# Directional_Coupler.net
KiCad netlist of a schematic drawn in Altium Designer
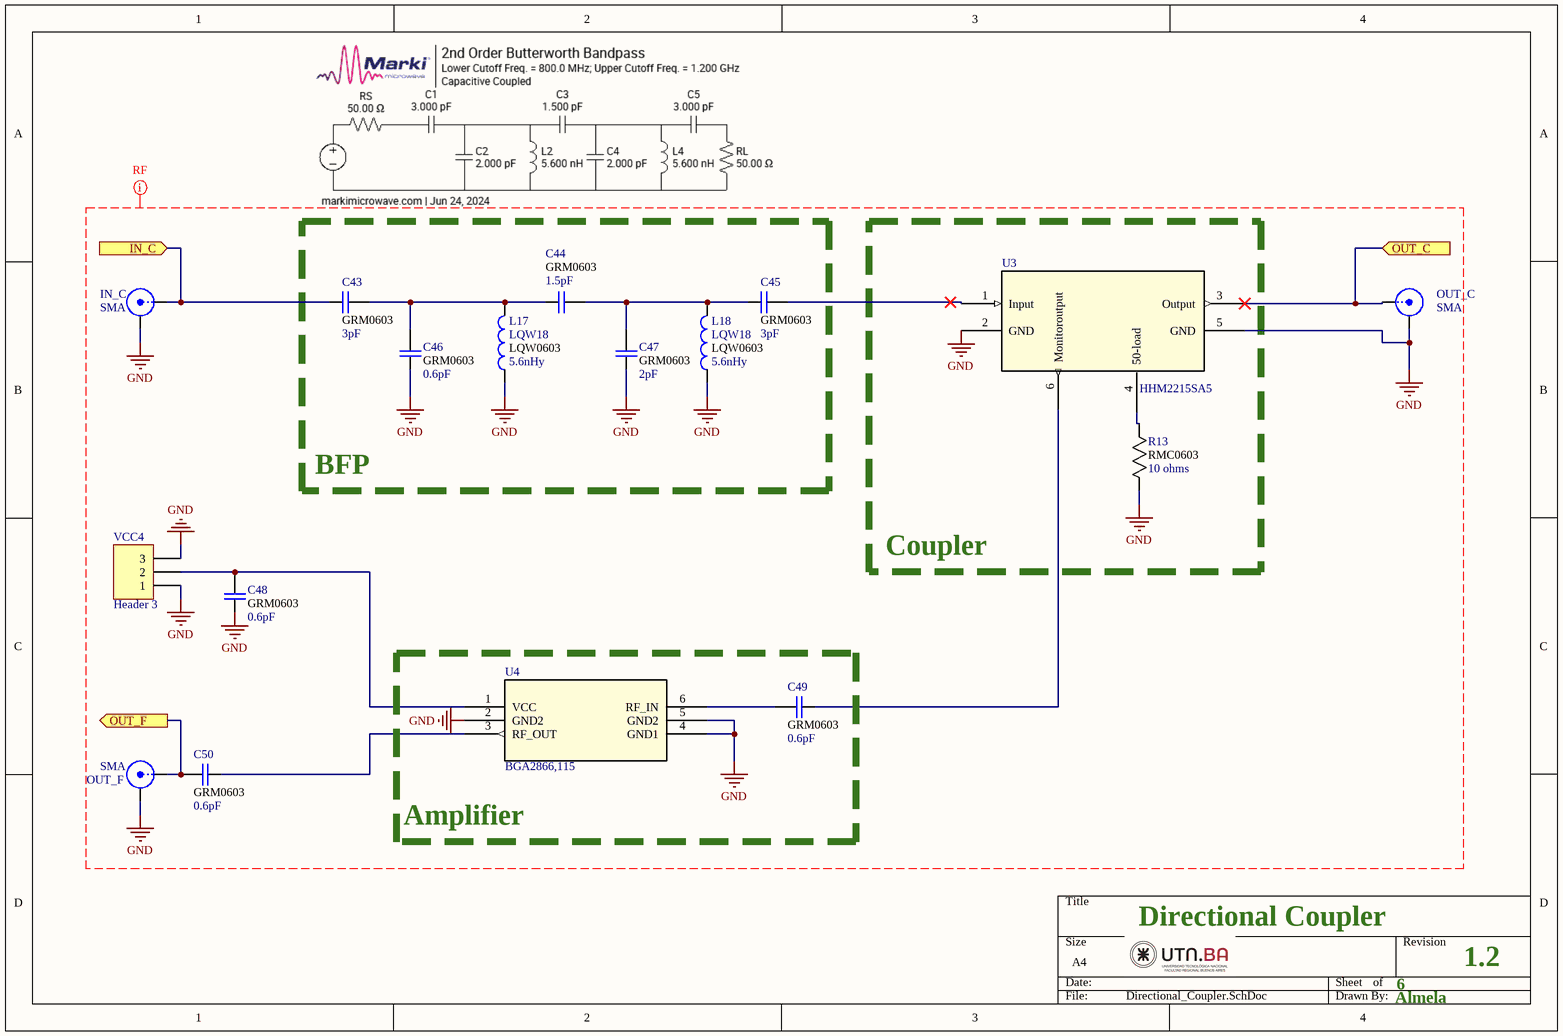
[diagram p0: Directional_Coupler.SchDoc]

(export (version "E")
  (design (tool "Eeschema 10.0.6"))
  (components
    (comp (ref "C43")
      (value "3pF")
      (footprint "GRM0603")
      (description "Capacitor GRM18 0603")
      (fields (field (name "Comment") "Cap 0603") (field (name "PUBLISHER") "Altium Limited"))
      (libsource (lib "Radar_RF_EAIII") (part "Cap"))
    )
    (comp (ref "C44")
      (value "1.5pF")
      (footprint "GRM0603")
      (description "Capacitor GRM18 0603")
      (fields (field (name "Comment") "Cap 0603") (field (name "PUBLISHER") "Altium Limited"))
      (libsource (lib "Radar_RF_EAIII") (part "Cap"))
    )
    (comp (ref "C45")
      (value "3pF")
      (footprint "GRM0603")
      (description "Capacitor GRM18 0603")
      (fields (field (name "Comment") "Cap 0603") (field (name "PUBLISHER") "Altium Limited"))
      (libsource (lib "Radar_RF_EAIII") (part "Cap"))
    )
    (comp (ref "C46")
      (value "0.6pF")
      (footprint "GRM0603")
      (description "Capacitor GRM18 0603")
      (fields (field (name "Comment") "Cap 0603") (field (name "PUBLISHER") "Altium Limited"))
      (libsource (lib "Radar_RF_EAIII") (part "Cap"))
    )
    (comp (ref "C47")
      (value "2pF")
      (footprint "GRM0603")
      (description "Capacitor GRM18 0603")
      (fields (field (name "Comment") "Cap 0603") (field (name "PUBLISHER") "Altium Limited"))
      (libsource (lib "Radar_RF_EAIII") (part "Cap"))
    )
    (comp (ref "C48")
      (value "0.6pF")
      (footprint "GRM0603")
      (description "Capacitor GRM18 0603")
      (fields (field (name "Comment") "Cap 0603") (field (name "PUBLISHER") "Altium Limited"))
      (libsource (lib "Radar_RF_EAIII") (part "Cap"))
    )
    (comp (ref "C49")
      (value "0.6pF")
      (footprint "GRM0603")
      (description "Capacitor GRM18 0603")
      (fields (field (name "Comment") "Cap 0603") (field (name "PUBLISHER") "Altium Limited"))
      (libsource (lib "Radar_RF_EAIII") (part "Cap"))
    )
    (comp (ref "C50")
      (value "0.6pF")
      (footprint "GRM0603")
      (description "Capacitor GRM18 0603")
      (fields (field (name "Comment") "Cap 0603") (field (name "PUBLISHER") "Altium Limited"))
      (libsource (lib "Radar_RF_EAIII") (part "Cap"))
    )
    (comp (ref "IN_C")
      (value "SMA")
      (footprint "SMA-142-0701-851")
      (description "SMA Straight Connector")
      (fields (field (name "PUBLISHER") "Altium Limited"))
      (libsource (lib "Radar_RF_EAIII") (part "SMA"))
    )
    (comp (ref "L17")
      (value "LQW18")
      (footprint "INDC1608X100N")
      (description "Ind RF Chip Wirewound 18nH 5% 100MHz 40Q-Factor 550mA 0603 Paper T/R")
      (fields
        (field (name "MP") "LQW18AN18NJ00D")
        (field (name "PARAMETER 1") "LQW0603")
        (field (name "ALTIUM_VALUE") "5.6nHy")
      )
      (libsource (lib "Radar_RF_EAIII") (part "LQW18"))
    )
    (comp (ref "L18")
      (value "LQW18")
      (footprint "INDC1608X100N")
      (description "Ind RF Chip Wirewound 18nH 5% 100MHz 40Q-Factor 550mA 0603 Paper T/R")
      (fields
        (field (name "MP") "LQW18AN18NJ00D")
        (field (name "PARAMETER 1") "LQW0603")
        (field (name "ALTIUM_VALUE") "5.6nHy")
      )
      (libsource (lib "Radar_RF_EAIII") (part "LQW18"))
    )
    (comp (ref "OUT_C")
      (value "SMA")
      (footprint "SMA-142-0701-851")
      (description "SMA Straight Connector")
      (fields (field (name "PUBLISHER") "Altium Limited"))
      (libsource (lib "Radar_RF_EAIII") (part "SMA"))
    )
    (comp (ref "OUT_F")
      (value "SMA")
      (footprint "SMA-142-0701-851")
      (description "SMB Straight Connector")
      (fields (field (name "PUBLISHER") "Altium Limited"))
      (libsource (lib "PCB_Project") (part "SMB"))
    )
    (comp (ref "R13")
      (value "10 ohms")
      (footprint "RMC0603")
      (description "Resistor RMC0603")
      (fields (field (name "Comment") "Resistor"))
      (libsource (lib "Radar_RF_EAIII") (part "Resistor"))
    )
    (comp (ref "U3")
      (value "HHM2215SA5")
      (footprint "HHM-6_1P6X0P8")
      (description "No Description Available")
      (libsource (lib "Radar_RF_EAIII") (part "HHM2215SA5"))
    )
    (comp (ref "U4")
      (value "BGA2866,115")
      (footprint "SOT363_NXP")
      (description "No Description Available")
      (libsource (lib "Radar_RF_EAIII") (part "BGA2866,115"))
    )
    (comp (ref "VCC4")
      (value "Header 3")
      (footprint "HDR1X3")
      (description "Header, 3-Pin")
      (fields (field (name "PUBLISHER") "Altium Limited"))
      (libsource (lib "Miscellaneous Connectors") (part "Header 3"))
    )
  )
  (nets
    (net (code "1") (name "/IN_C") (class "Default")
      (node (ref "C43") (pin "1") (pinfunction "1_1") (pintype "passive"))
      (node (ref "IN_C") (pin "1") (pinfunction "X_1") (pintype "passive"))
    )
    (net (code "2") (name "/OUT_C") (class "Default")
      (node (ref "OUT_C") (pin "1") (pinfunction "X_1") (pintype "passive"))
      (node (ref "U3") (pin "3") (pinfunction "Output_3") (pintype "output"))
    )
    (net (code "3") (name "/OUT_F") (class "Default")
      (node (ref "C50") (pin "2") (pinfunction "2_2") (pintype "passive"))
      (node (ref "OUT_F") (pin "1") (pinfunction "X_1") (pintype "passive"))
    )
    (net (code "4") (name "GND") (class "Default")
      (node (ref "C46") (pin "1") (pinfunction "1_1") (pintype "passive"))
      (node (ref "C47") (pin "1") (pinfunction "1_1") (pintype "passive"))
      (node (ref "C48") (pin "1") (pinfunction "1_1") (pintype "passive"))
      (node (ref "IN_C") (pin "2") (pinfunction "Y_2") (pintype "passive"))
      (node (ref "L17") (pin "1") (pinfunction "1_1") (pintype "passive"))
      (node (ref "L18") (pin "1") (pinfunction "1_1") (pintype "passive"))
      (node (ref "OUT_C") (pin "2") (pinfunction "Y_2") (pintype "passive"))
      (node (ref "OUT_F") (pin "2") (pinfunction "Y_2") (pintype "passive"))
      (node (ref "R13") (pin "1") (pinfunction "1_1") (pintype "passive"))
      (node (ref "U3") (pin "2") (pinfunction "GND_2") (pintype "power_in"))
      (node (ref "U3") (pin "5") (pinfunction "GND_5") (pintype "power_in"))
      (node (ref "U4") (pin "2") (pinfunction "GND2_2") (pintype "power_in"))
      (node (ref "U4") (pin "4") (pinfunction "GND1_4") (pintype "power_in"))
      (node (ref "U4") (pin "5") (pinfunction "GND2_5") (pintype "power_in"))
      (node (ref "VCC4") (pin "1") (pinfunction "1_1") (pintype "passive"))
      (node (ref "VCC4") (pin "3") (pinfunction "3_3") (pintype "passive"))
    )
    (net (code "5") (name "Net-(C43-Pad2)") (class "Default")
      (node (ref "C43") (pin "2") (pinfunction "2_2") (pintype "passive"))
      (node (ref "C44") (pin "1") (pinfunction "1_1") (pintype "passive"))
      (node (ref "C46") (pin "2") (pinfunction "2_2") (pintype "passive"))
      (node (ref "L17") (pin "2") (pinfunction "2_2") (pintype "passive"))
    )
    (net (code "6") (name "Net-(C44-Pad2)") (class "Default")
      (node (ref "C44") (pin "2") (pinfunction "2_2") (pintype "passive"))
      (node (ref "C45") (pin "1") (pinfunction "1_1") (pintype "passive"))
      (node (ref "C47") (pin "2") (pinfunction "2_2") (pintype "passive"))
      (node (ref "L18") (pin "2") (pinfunction "2_2") (pintype "passive"))
    )
    (net (code "7") (name "Net-(U3-50-load)") (class "Default")
      (node (ref "R13") (pin "2") (pinfunction "2_2") (pintype "passive"))
      (node (ref "U3") (pin "4") (pinfunction "50-load_4") (pintype "passive"))
    )
    (net (code "8") (name "Net-(U3-Input)") (class "Default")
      (node (ref "C45") (pin "2") (pinfunction "2_2") (pintype "passive"))
      (node (ref "U3") (pin "1") (pinfunction "Input_1") (pintype "input"))
    )
    (net (code "9") (name "Net-(U3-Monitoroutput)") (class "Default")
      (node (ref "C49") (pin "1") (pinfunction "1_1") (pintype "passive"))
      (node (ref "U3") (pin "6") (pinfunction "Monitoroutput_6") (pintype "output"))
    )
    (net (code "10") (name "Net-(U4-RF_IN)") (class "Default")
      (node (ref "C49") (pin "2") (pinfunction "2_2") (pintype "passive"))
      (node (ref "U4") (pin "6") (pinfunction "RF_IN_6") (pintype "passive"))
    )
    (net (code "11") (name "Net-(U4-RF_OUT)") (class "Default")
      (node (ref "C50") (pin "1") (pinfunction "1_1") (pintype "passive"))
      (node (ref "U4") (pin "3") (pinfunction "RF_OUT_3") (pintype "output"))
    )
    (net (code "12") (name "Net-(U4-VCC)") (class "Default")
      (node (ref "C48") (pin "2") (pinfunction "2_2") (pintype "passive"))
      (node (ref "U4") (pin "1") (pinfunction "VCC_1") (pintype "power_in"))
      (node (ref "VCC4") (pin "2") (pinfunction "2_2") (pintype "passive"))
    )
  )
)
